# schematic.net
KiCad netlist of a schematic drawn in Altium Designer
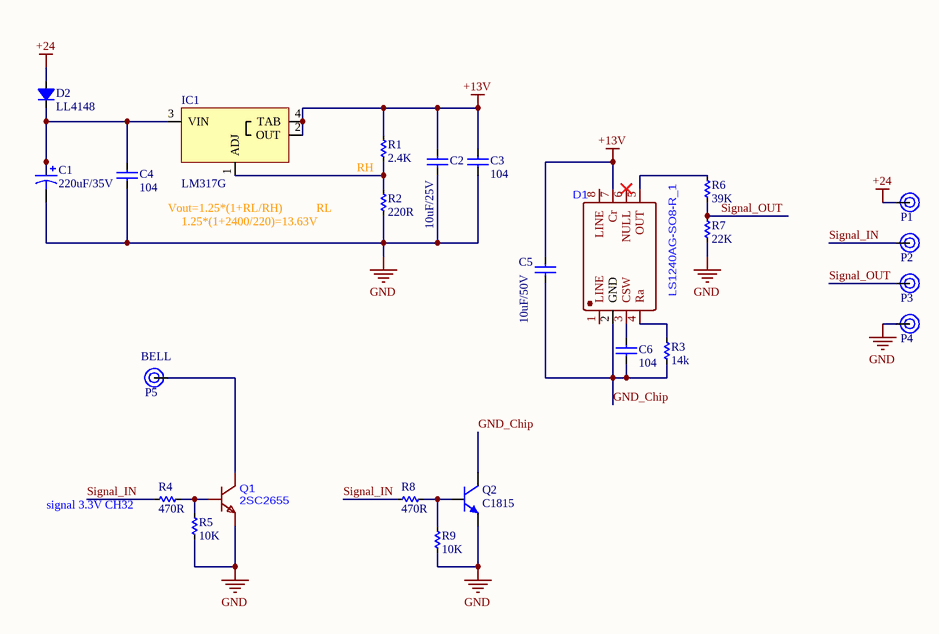
[diagram p0: schematic.SchDoc]

(export (version "E")
  (design (tool "Eeschema 10.0.6"))
  (components
    (comp (ref "C1")
      (value "220uF/35V")
      (footprint "C8X12mm")
      (description "Polarized Capacitor (Axial) 220uF 35V")
      (libsource (lib "RD Integrated_Library") (part "Cap Pol 220uF/35V"))
    )
    (comp (ref "C2")
      (value "10uF/25V")
      (footprint "C_0805_SMD")
      (description "Cap SMD 0805 10uF")
      (libsource (lib "RD Integrated_Library") (part "Cap 0805 10uF 25V"))
    )
    (comp (ref "C3")
      (value "104")
      (footprint "C_0805_SMD")
      (description "Cap SMD 0805 104-100nF-0.1uF 50V")
      (libsource (lib "RD Integrated_Library") (part "Cap 0805 104 100nF"))
    )
    (comp (ref "C4")
      (value "104")
      (footprint "C_0805_SMD")
      (description "Cap SMD 0805 104-100nF-0.1uF 50V")
      (libsource (lib "RD Integrated_Library") (part "Cap 0805 104 100nF"))
    )
    (comp (ref "C5")
      (value "10uF/50V")
      (footprint "C_0805_SMD")
      (description "Cap SMD 0805 10uF 50V")
      (libsource (lib "RD Integrated_Library") (part "Cap 0805 10uF 50V"))
    )
    (comp (ref "C6")
      (value "104")
      (footprint "C_0805_SMD")
      (description "Cap SMD 0805 104-100nF-0.1uF 50V")
      (libsource (lib "RD Integrated_Library") (part "Cap 0805 104 100nF"))
    )
    (comp (ref "D1")
      (value "LS1240AG-SO8-R_1")
      (footprint "LS1240AG-SO8-R")
      (libsource (lib "LibVinaFe") (part "LS1240AG-SO8-R_1"))
    )
    (comp (ref "D2")
      (value "LL4148")
      (footprint "SOD80C_MFG")
      (description "0.2A, 100V, SOD80")
      (fields (field (name "DESIGNED BY") "Nhox"))
      (libsource (lib "RD Integrated_Library") (part "LL4148"))
    )
    (comp (ref "IC1")
      (value "LM317G")
      (footprint "SOT223-4N")
      (description "HIGH CURRENT 1.3V TO 37V ADJUSTABLE VOLTAGE REGULATOR")
      (fields (field (name "DESIGNED BY") "TranLuyen"))
      (libsource (lib "RD Integrated_Library") (part "LM317G"))
    )
    (comp (ref "P1")
      (value "Pad 1.5mm")
      (footprint "Pad 1.5mm 3mm")
      (libsource (lib "RD Integrated_Library") (part "Pad 1.5mm 3mm"))
    )
    (comp (ref "P2")
      (value "Pad 1.5mm")
      (footprint "Pad 1.5mm 3mm")
      (libsource (lib "RD Integrated_Library") (part "Pad 1.5mm 3mm"))
    )
    (comp (ref "P3")
      (value "Pad 1.5mm")
      (footprint "Pad 1.5mm 3mm")
      (libsource (lib "RD Integrated_Library") (part "Pad 1.5mm 3mm"))
    )
    (comp (ref "P4")
      (value "Pad 1.5mm")
      (footprint "Pad 1.5mm 3mm")
      (libsource (lib "RD Integrated_Library") (part "Pad 1.5mm 3mm"))
    )
    (comp (ref "P5")
      (value "Pad 1.5mm")
      (footprint "Pad 1.5mm 3mm")
      (libsource (lib "RD Integrated_Library") (part "Pad 1.5mm 3mm"))
    )
    (comp (ref "Q1") (value "2SC2655") (footprint "2SC2655") (libsource (lib "LibVinaFe") (part "2SC2655")))
    (comp (ref "Q2")
      (value "C1815")
      (footprint "SOT23_N NXP")
      (description "NPN SMD Transistor SOT23")
      (libsource (lib "RD Integrated_Library") (part "C1815 SMD SOT-23"))
    )
    (comp (ref "R1")
      (value "2.4K")
      (footprint "RES-SMD-0805")
      (description "Resistor SMD 0805")
      (libsource (lib "RD Integrated_Library") (part "Res 2.4k 0805"))
    )
    (comp (ref "R2")
      (value "220R")
      (footprint "RES-SMD-0805")
      (description "Resistor SMD 0805")
      (libsource (lib "RD Integrated_Library") (part "Res 220R 0805"))
    )
    (comp (ref "R3")
      (value "14k")
      (footprint "RES-SMD-0805")
      (description "Resistor SMD 0805, 14k Ohm")
      (libsource (lib "RD Integrated_Library") (part "Res 13K 0805"))
    )
    (comp (ref "R4")
      (value "470R")
      (footprint "RES-SMD-0805")
      (description "Resistor SMD 0805")
      (libsource (lib "RD Integrated_Library") (part "Res 470R 0805"))
    )
    (comp (ref "R5")
      (value "10K")
      (footprint "RES-SMD-0805")
      (description "Resistor SMD 0805")
      (libsource (lib "RD Integrated_Library") (part "Res 10k 0805"))
    )
    (comp (ref "R6")
      (value "39K")
      (footprint "RES-SMD-0805")
      (description "Resistor SMD 0805")
      (libsource (lib "RD Integrated_Library") (part "Res 39K 0805"))
    )
    (comp (ref "R7")
      (value "22K")
      (footprint "RES-SMD-0805")
      (description "Resistor SMD 0805")
      (libsource (lib "RD Integrated_Library") (part "Res 22K 0805"))
    )
    (comp (ref "R8")
      (value "470R")
      (footprint "RES-SMD-0805")
      (description "Resistor SMD 0805")
      (libsource (lib "RD Integrated_Library") (part "Res 470R 0805"))
    )
    (comp (ref "R9")
      (value "10K")
      (footprint "RES-SMD-0805")
      (description "Resistor SMD 0805")
      (libsource (lib "RD Integrated_Library") (part "Res 10k 0805"))
    )
  )
  (nets
    (net (code "1") (name "+13V") (class "Default")
      (node (ref "C2") (pin "2") (pinfunction "2_2") (pintype "passive"))
      (node (ref "C3") (pin "2") (pinfunction "2_2") (pintype "passive"))
      (node (ref "C5") (pin "2") (pinfunction "2_2") (pintype "passive"))
      (node (ref "D1") (pin "7") (pinfunction "Cr_7") (pintype "passive"))
      (node (ref "IC1") (pin "2") (pinfunction "OUT_2") (pintype "passive"))
      (node (ref "IC1") (pin "4") (pinfunction "TAB_4") (pintype "passive"))
      (node (ref "R1") (pin "1") (pinfunction "1_1") (pintype "passive"))
    )
    (net (code "2") (name "+24") (class "Default")
      (node (ref "D2") (pin "2") (pinfunction "2_2") (pintype "passive"))
      (node (ref "P1") (pin "1") (pintype "passive"))
    )
    (net (code "3") (name "/GND_Chip") (class "Default")
      (node (ref "C5") (pin "1") (pinfunction "1_1") (pintype "passive"))
      (node (ref "C6") (pin "1") (pinfunction "1_1") (pintype "passive"))
      (node (ref "D1") (pin "2") (pinfunction "GND_2") (pintype "passive"))
      (node (ref "Q2") (pin "3") (pinfunction "C_3") (pintype "passive"))
      (node (ref "R3") (pin "2") (pinfunction "2_2") (pintype "passive"))
    )
    (net (code "4") (name "/Signal_IN") (class "Default")
      (node (ref "P2") (pin "1") (pintype "passive"))
      (node (ref "R4") (pin "2") (pinfunction "2_2") (pintype "passive"))
      (node (ref "R8") (pin "2") (pinfunction "2_2") (pintype "passive"))
    )
    (net (code "5") (name "/Signal_OUT") (class "Default")
      (node (ref "P3") (pin "1") (pintype "passive"))
      (node (ref "R6") (pin "2") (pinfunction "2_2") (pintype "passive"))
      (node (ref "R7") (pin "1") (pinfunction "1_1") (pintype "passive"))
    )
    (net (code "6") (name "GND") (class "Default")
      (node (ref "C1") (pin "2") (pinfunction "2_2") (pintype "passive"))
      (node (ref "C2") (pin "1") (pinfunction "1_1") (pintype "passive"))
      (node (ref "C3") (pin "1") (pinfunction "1_1") (pintype "passive"))
      (node (ref "C4") (pin "1") (pinfunction "1_1") (pintype "passive"))
      (node (ref "P4") (pin "1") (pintype "passive"))
      (node (ref "Q1") (pin "1") (pinfunction "E_1") (pintype "passive"))
      (node (ref "Q2") (pin "2") (pinfunction "E_2") (pintype "passive"))
      (node (ref "R2") (pin "2") (pinfunction "2_2") (pintype "passive"))
      (node (ref "R5") (pin "2") (pinfunction "2_2") (pintype "passive"))
      (node (ref "R7") (pin "2") (pinfunction "2_2") (pintype "passive"))
      (node (ref "R9") (pin "2") (pinfunction "2_2") (pintype "passive"))
    )
    (net (code "7") (name "Net-(D1-CSW)") (class "Default")
      (node (ref "C6") (pin "2") (pinfunction "2_2") (pintype "passive"))
      (node (ref "D1") (pin "3") (pinfunction "CSW_3") (pintype "passive"))
    )
    (net (code "8") (name "Net-(D1-OUT)") (class "Default")
      (node (ref "D1") (pin "5") (pinfunction "OUT_5") (pintype "passive"))
      (node (ref "R6") (pin "1") (pinfunction "1_1") (pintype "passive"))
    )
    (net (code "9") (name "Net-(D1-Ra)") (class "Default")
      (node (ref "D1") (pin "4") (pinfunction "Ra_4") (pintype "passive"))
      (node (ref "R3") (pin "1") (pinfunction "1_1") (pintype "passive"))
    )
    (net (code "10") (name "Net-(IC1-ADJ)") (class "Default")
      (node (ref "IC1") (pin "1") (pinfunction "ADJ_1") (pintype "passive"))
      (node (ref "R1") (pin "2") (pinfunction "2_2") (pintype "passive"))
      (node (ref "R2") (pin "1") (pinfunction "1_1") (pintype "passive"))
    )
    (net (code "11") (name "Net-(IC1-VIN)") (class "Default")
      (node (ref "C1") (pin "1") (pinfunction "1_1") (pintype "passive"))
      (node (ref "C4") (pin "2") (pinfunction "2_2") (pintype "passive"))
      (node (ref "D2") (pin "1") (pinfunction "1_1") (pintype "passive"))
      (node (ref "IC1") (pin "3") (pinfunction "VIN_3") (pintype "passive"))
    )
    (net (code "12") (name "Net-(Q1-B)") (class "Default")
      (node (ref "Q1") (pin "3") (pinfunction "B_3") (pintype "passive"))
      (node (ref "R4") (pin "1") (pinfunction "1_1") (pintype "passive"))
      (node (ref "R5") (pin "1") (pinfunction "1_1") (pintype "passive"))
    )
    (net (code "13") (name "Net-(Q1-C)") (class "Default")
      (node (ref "P5") (pin "1") (pintype "passive"))
      (node (ref "Q1") (pin "2") (pinfunction "C_2") (pintype "passive"))
    )
    (net (code "14") (name "Net-(Q2-B)") (class "Default")
      (node (ref "Q2") (pin "1") (pinfunction "B_1") (pintype "passive"))
      (node (ref "R8") (pin "1") (pinfunction "1_1") (pintype "passive"))
      (node (ref "R9") (pin "1") (pinfunction "1_1") (pintype "passive"))
    )
    (net (code "15") (name "unconnected-(D1-LINE-Pad1)") (class "Default")
      (node (ref "D1") (pin "1") (pinfunction "LINE_1") (pintype "passive"))
    )
    (net (code "16") (name "unconnected-(D1-LINE-Pad8)") (class "Default")
      (node (ref "D1") (pin "8") (pinfunction "LINE_8") (pintype "passive"))
    )
    (net (code "17") (name "unconnected-(D1-NULL-Pad6)") (class "Default")
      (node (ref "D1") (pin "6") (pinfunction "NULL_6") (pintype "passive+no_connect"))
    )
  )
)
